# KitchenLightsController.net
KiCad netlist of a schematic drawn in EAGLE
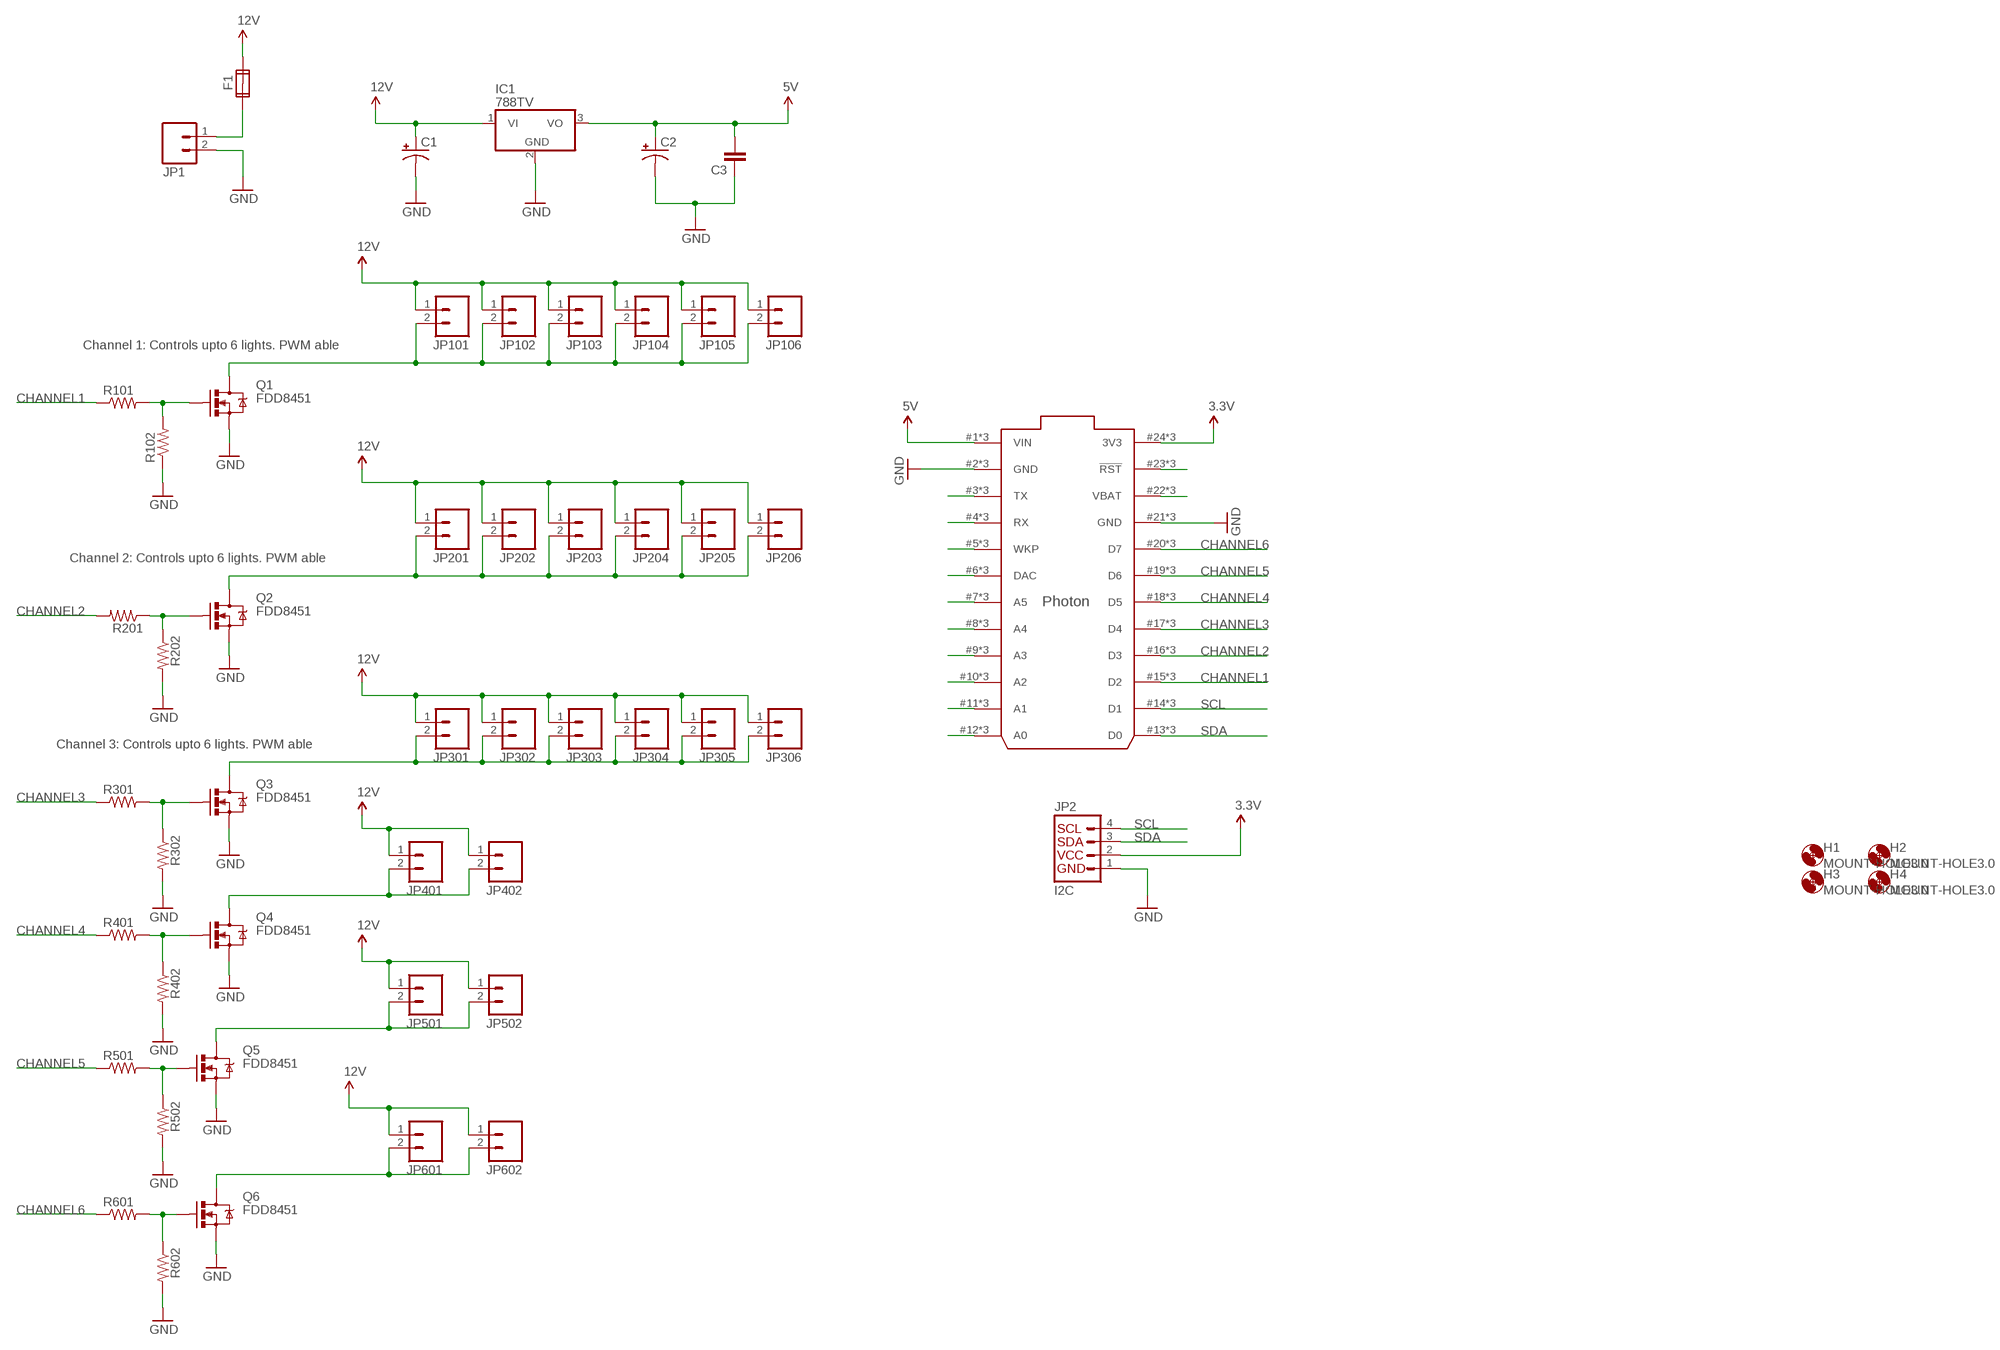
[diagram p0: schematic, sheet 1, part 1 of 2]
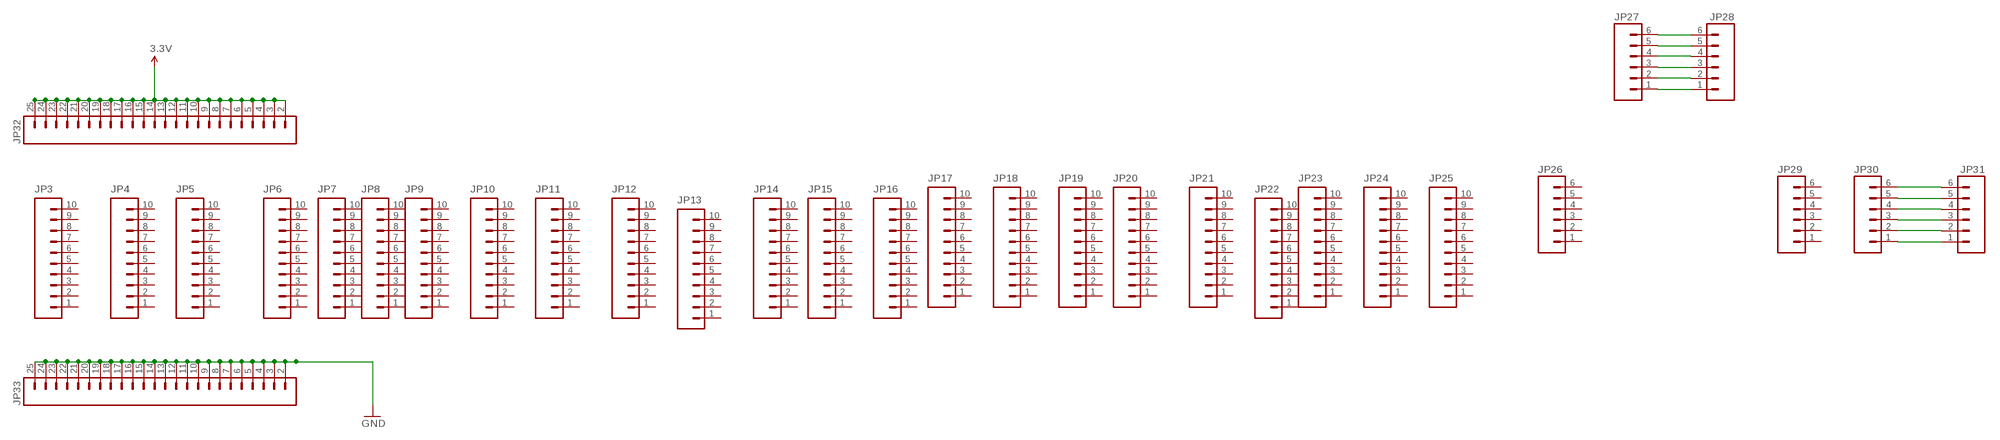
[diagram p1: schematic, sheet 1, part 2 of 2]

(export (version "E")
  (design (tool "Eeschema 10.0.6"))
  (components
    (comp (ref "C1")
      (value "10UF-25V-20%(PTH)")
      (footprint "eagle-import:CPOL-RADIAL-10UF-25V")
      (libsource (lib "eagle-import") (part "10UF-25V-20%(PTH)"))
    )
    (comp (ref "C2")
      (value "10UF-25V-20%(PTH)")
      (footprint "eagle-import:CPOL-RADIAL-10UF-25V")
      (libsource (lib "eagle-import") (part "10UF-25V-20%(PTH)"))
    )
    (comp (ref "C3")
      (value "1UF-25V-10%(0805)\"")
      (footprint "eagle-import:0805-CAP")
      (libsource (lib "eagle-import") (part "1UF-25V-10%(0805){dblquote}"))
    )
    (comp (ref "F1")
      (value "FUSE2P")
      (footprint "eagle-import:FUSE1")
      (libsource (lib "eagle-import") (part "FUSE2P"))
    )
    (comp (ref "H1")
      (value "MOUNT-HOLE3.0")
      (footprint "eagle-import:3,0")
      (libsource (lib "eagle-import") (part "MOUNT-HOLE3.0"))
    )
    (comp (ref "H2")
      (value "MOUNT-HOLE3.0")
      (footprint "eagle-import:3,0")
      (libsource (lib "eagle-import") (part "MOUNT-HOLE3.0"))
    )
    (comp (ref "H3")
      (value "MOUNT-HOLE3.0")
      (footprint "eagle-import:3,0")
      (libsource (lib "eagle-import") (part "MOUNT-HOLE3.0"))
    )
    (comp (ref "H4")
      (value "MOUNT-HOLE3.0")
      (footprint "eagle-import:3,0")
      (libsource (lib "eagle-import") (part "MOUNT-HOLE3.0"))
    )
    (comp (ref "IC1")
      (value "788TV")
      (footprint "eagle-import:TO220V")
      (libsource (lib "eagle-import") (part "78TV8"))
    )
    (comp (ref "JP1")
      (value "M023.5MM")
      (footprint "eagle-import:SCREWTERMINAL-3.5MM-2")
      (libsource (lib "eagle-import") (part "M023.5MM"))
    )
    (comp (ref "JP2")
      (value "I2C")
      (footprint "eagle-import:1X04")
      (libsource (lib "eagle-import") (part "I2C_STANDARD"))
    )
    (comp (ref "JP3")
      (value "M10NO_SILK_PTH_FEMALE")
      (footprint "eagle-import:1X10_NO_SILK")
      (libsource (lib "eagle-import") (part "M10NO_SILK_PTH_FEMALE"))
    )
    (comp (ref "JP4")
      (value "M10NO_SILK_PTH_FEMALE")
      (footprint "eagle-import:1X10_NO_SILK")
      (libsource (lib "eagle-import") (part "M10NO_SILK_PTH_FEMALE"))
    )
    (comp (ref "JP5")
      (value "M10NO_SILK_PTH_FEMALE")
      (footprint "eagle-import:1X10_NO_SILK")
      (libsource (lib "eagle-import") (part "M10NO_SILK_PTH_FEMALE"))
    )
    (comp (ref "JP6")
      (value "M10NO_SILK_PTH_FEMALE")
      (footprint "eagle-import:1X10_NO_SILK")
      (libsource (lib "eagle-import") (part "M10NO_SILK_PTH_FEMALE"))
    )
    (comp (ref "JP7")
      (value "M10NO_SILK_PTH_FEMALE")
      (footprint "eagle-import:1X10_NO_SILK")
      (libsource (lib "eagle-import") (part "M10NO_SILK_PTH_FEMALE"))
    )
    (comp (ref "JP8")
      (value "M10NO_SILK_PTH_FEMALE")
      (footprint "eagle-import:1X10_NO_SILK")
      (libsource (lib "eagle-import") (part "M10NO_SILK_PTH_FEMALE"))
    )
    (comp (ref "JP9")
      (value "M10NO_SILK_PTH_FEMALE")
      (footprint "eagle-import:1X10_NO_SILK")
      (libsource (lib "eagle-import") (part "M10NO_SILK_PTH_FEMALE"))
    )
    (comp (ref "JP10")
      (value "M10NO_SILK_PTH_FEMALE")
      (footprint "eagle-import:1X10_NO_SILK")
      (libsource (lib "eagle-import") (part "M10NO_SILK_PTH_FEMALE"))
    )
    (comp (ref "JP11")
      (value "M10NO_SILK_PTH_FEMALE")
      (footprint "eagle-import:1X10_NO_SILK")
      (libsource (lib "eagle-import") (part "M10NO_SILK_PTH_FEMALE"))
    )
    (comp (ref "JP12")
      (value "M10NO_SILK_PTH_FEMALE")
      (footprint "eagle-import:1X10_NO_SILK")
      (libsource (lib "eagle-import") (part "M10NO_SILK_PTH_FEMALE"))
    )
    (comp (ref "JP13")
      (value "M10NO_SILK_PTH_FEMALE")
      (footprint "eagle-import:1X10_NO_SILK")
      (libsource (lib "eagle-import") (part "M10NO_SILK_PTH_FEMALE"))
    )
    (comp (ref "JP14")
      (value "M10NO_SILK_PTH_FEMALE")
      (footprint "eagle-import:1X10_NO_SILK")
      (libsource (lib "eagle-import") (part "M10NO_SILK_PTH_FEMALE"))
    )
    (comp (ref "JP15")
      (value "M10NO_SILK_PTH_FEMALE")
      (footprint "eagle-import:1X10_NO_SILK")
      (libsource (lib "eagle-import") (part "M10NO_SILK_PTH_FEMALE"))
    )
    (comp (ref "JP16")
      (value "M10NO_SILK_PTH_FEMALE")
      (footprint "eagle-import:1X10_NO_SILK")
      (libsource (lib "eagle-import") (part "M10NO_SILK_PTH_FEMALE"))
    )
    (comp (ref "JP17")
      (value "M10NO_SILK_PTH_FEMALE")
      (footprint "eagle-import:1X10_NO_SILK")
      (libsource (lib "eagle-import") (part "M10NO_SILK_PTH_FEMALE"))
    )
    (comp (ref "JP18")
      (value "M10NO_SILK_PTH_FEMALE")
      (footprint "eagle-import:1X10_NO_SILK")
      (libsource (lib "eagle-import") (part "M10NO_SILK_PTH_FEMALE"))
    )
    (comp (ref "JP19")
      (value "M10NO_SILK_PTH_FEMALE")
      (footprint "eagle-import:1X10_NO_SILK")
      (libsource (lib "eagle-import") (part "M10NO_SILK_PTH_FEMALE"))
    )
    (comp (ref "JP20")
      (value "M10NO_SILK_PTH_FEMALE")
      (footprint "eagle-import:1X10_NO_SILK")
      (libsource (lib "eagle-import") (part "M10NO_SILK_PTH_FEMALE"))
    )
    (comp (ref "JP21")
      (value "M10NO_SILK_PTH_FEMALE")
      (footprint "eagle-import:1X10_NO_SILK")
      (libsource (lib "eagle-import") (part "M10NO_SILK_PTH_FEMALE"))
    )
    (comp (ref "JP22")
      (value "M10NO_SILK_PTH_FEMALE")
      (footprint "eagle-import:1X10_NO_SILK")
      (libsource (lib "eagle-import") (part "M10NO_SILK_PTH_FEMALE"))
    )
    (comp (ref "JP23")
      (value "M10NO_SILK_PTH_FEMALE")
      (footprint "eagle-import:1X10_NO_SILK")
      (libsource (lib "eagle-import") (part "M10NO_SILK_PTH_FEMALE"))
    )
    (comp (ref "JP24")
      (value "M10NO_SILK_PTH_FEMALE")
      (footprint "eagle-import:1X10_NO_SILK")
      (libsource (lib "eagle-import") (part "M10NO_SILK_PTH_FEMALE"))
    )
    (comp (ref "JP25")
      (value "M10NO_SILK_PTH_FEMALE")
      (footprint "eagle-import:1X10_NO_SILK")
      (libsource (lib "eagle-import") (part "M10NO_SILK_PTH_FEMALE"))
    )
    (comp (ref "JP26")
      (value "M06NO_SILK_FEMALE_PTH")
      (footprint "eagle-import:1X06_NO_SILK")
      (libsource (lib "eagle-import") (part "M06NO_SILK_FEMALE_PTH"))
    )
    (comp (ref "JP27")
      (value "M06NO_SILK_FEMALE_PTH")
      (footprint "eagle-import:1X06_NO_SILK")
      (libsource (lib "eagle-import") (part "M06NO_SILK_FEMALE_PTH"))
    )
    (comp (ref "JP28")
      (value "M06NO_SILK_FEMALE_PTH")
      (footprint "eagle-import:1X06_NO_SILK")
      (libsource (lib "eagle-import") (part "M06NO_SILK_FEMALE_PTH"))
    )
    (comp (ref "JP29")
      (value "M06NO_SILK_FEMALE_PTH")
      (footprint "eagle-import:1X06_NO_SILK")
      (libsource (lib "eagle-import") (part "M06NO_SILK_FEMALE_PTH"))
    )
    (comp (ref "JP30")
      (value "M06NO_SILK_FEMALE_PTH")
      (footprint "eagle-import:1X06_NO_SILK")
      (libsource (lib "eagle-import") (part "M06NO_SILK_FEMALE_PTH"))
    )
    (comp (ref "JP31")
      (value "M06NO_SILK_FEMALE_PTH")
      (footprint "eagle-import:1X06_NO_SILK")
      (libsource (lib "eagle-import") (part "M06NO_SILK_FEMALE_PTH"))
    )
    (comp (ref "JP32")
      (value "M24")
      (footprint "eagle-import:1X24")
      (libsource (lib "eagle-import") (part "M24"))
    )
    (comp (ref "JP33")
      (value "M24")
      (footprint "eagle-import:1X24")
      (libsource (lib "eagle-import") (part "M24"))
    )
    (comp (ref "JP101")
      (value "M02POLAR")
      (footprint "eagle-import:MOLEX-1X2")
      (libsource (lib "eagle-import") (part "M02POLAR"))
    )
    (comp (ref "JP102")
      (value "M02POLAR")
      (footprint "eagle-import:MOLEX-1X2")
      (libsource (lib "eagle-import") (part "M02POLAR"))
    )
    (comp (ref "JP103")
      (value "M02POLAR")
      (footprint "eagle-import:MOLEX-1X2")
      (libsource (lib "eagle-import") (part "M02POLAR"))
    )
    (comp (ref "JP104")
      (value "M02POLAR")
      (footprint "eagle-import:MOLEX-1X2")
      (libsource (lib "eagle-import") (part "M02POLAR"))
    )
    (comp (ref "JP105")
      (value "M02POLAR")
      (footprint "eagle-import:MOLEX-1X2")
      (libsource (lib "eagle-import") (part "M02POLAR"))
    )
    (comp (ref "JP106")
      (value "M02POLAR")
      (footprint "eagle-import:MOLEX-1X2")
      (libsource (lib "eagle-import") (part "M02POLAR"))
    )
    (comp (ref "JP201")
      (value "M02POLAR")
      (footprint "eagle-import:MOLEX-1X2")
      (libsource (lib "eagle-import") (part "M02POLAR"))
    )
    (comp (ref "JP202")
      (value "M02POLAR")
      (footprint "eagle-import:MOLEX-1X2")
      (libsource (lib "eagle-import") (part "M02POLAR"))
    )
    (comp (ref "JP203")
      (value "M02POLAR")
      (footprint "eagle-import:MOLEX-1X2")
      (libsource (lib "eagle-import") (part "M02POLAR"))
    )
    (comp (ref "JP204")
      (value "M02POLAR")
      (footprint "eagle-import:MOLEX-1X2")
      (libsource (lib "eagle-import") (part "M02POLAR"))
    )
    (comp (ref "JP205")
      (value "M02POLAR")
      (footprint "eagle-import:MOLEX-1X2")
      (libsource (lib "eagle-import") (part "M02POLAR"))
    )
    (comp (ref "JP206")
      (value "M02POLAR")
      (footprint "eagle-import:MOLEX-1X2")
      (libsource (lib "eagle-import") (part "M02POLAR"))
    )
    (comp (ref "JP301")
      (value "M02POLAR")
      (footprint "eagle-import:MOLEX-1X2")
      (libsource (lib "eagle-import") (part "M02POLAR"))
    )
    (comp (ref "JP302")
      (value "M02POLAR")
      (footprint "eagle-import:MOLEX-1X2")
      (libsource (lib "eagle-import") (part "M02POLAR"))
    )
    (comp (ref "JP303")
      (value "M02POLAR")
      (footprint "eagle-import:MOLEX-1X2")
      (libsource (lib "eagle-import") (part "M02POLAR"))
    )
    (comp (ref "JP304")
      (value "M02POLAR")
      (footprint "eagle-import:MOLEX-1X2")
      (libsource (lib "eagle-import") (part "M02POLAR"))
    )
    (comp (ref "JP305")
      (value "M02POLAR")
      (footprint "eagle-import:MOLEX-1X2")
      (libsource (lib "eagle-import") (part "M02POLAR"))
    )
    (comp (ref "JP306")
      (value "M02POLAR")
      (footprint "eagle-import:MOLEX-1X2")
      (libsource (lib "eagle-import") (part "M02POLAR"))
    )
    (comp (ref "JP401")
      (value "M02POLAR")
      (footprint "eagle-import:MOLEX-1X2")
      (libsource (lib "eagle-import") (part "M02POLAR"))
    )
    (comp (ref "JP402")
      (value "M023.5MM")
      (footprint "eagle-import:SCREWTERMINAL-3.5MM-2")
      (libsource (lib "eagle-import") (part "M023.5MM"))
    )
    (comp (ref "JP501")
      (value "M02POLAR")
      (footprint "eagle-import:MOLEX-1X2")
      (libsource (lib "eagle-import") (part "M02POLAR"))
    )
    (comp (ref "JP502")
      (value "M023.5MM")
      (footprint "eagle-import:SCREWTERMINAL-3.5MM-2")
      (libsource (lib "eagle-import") (part "M023.5MM"))
    )
    (comp (ref "JP601")
      (value "M02POLAR")
      (footprint "eagle-import:MOLEX-1X2")
      (libsource (lib "eagle-import") (part "M02POLAR"))
    )
    (comp (ref "JP602")
      (value "M023.5MM")
      (footprint "eagle-import:SCREWTERMINAL-3.5MM-2")
      (libsource (lib "eagle-import") (part "M023.5MM"))
    )
    (comp (ref "Q1")
      (value "FDD8451")
      (footprint "eagle-import:DPAK")
      (libsource (lib "eagle-import") (part "MOSFET-NCHANNELFDD8780"))
    )
    (comp (ref "Q2")
      (value "FDD8451")
      (footprint "eagle-import:DPAK")
      (libsource (lib "eagle-import") (part "MOSFET-NCHANNELFDD8780"))
    )
    (comp (ref "Q3")
      (value "FDD8451")
      (footprint "eagle-import:DPAK")
      (libsource (lib "eagle-import") (part "MOSFET-NCHANNELFDD8780"))
    )
    (comp (ref "Q4")
      (value "FDD8451")
      (footprint "eagle-import:DPAK")
      (libsource (lib "eagle-import") (part "MOSFET-NCHANNELFDD8780"))
    )
    (comp (ref "Q5")
      (value "FDD8451")
      (footprint "eagle-import:DPAK")
      (libsource (lib "eagle-import") (part "MOSFET-NCHANNELFDD8780"))
    )
    (comp (ref "Q6")
      (value "FDD8451")
      (footprint "eagle-import:DPAK")
      (libsource (lib "eagle-import") (part "MOSFET-NCHANNELFDD8780"))
    )
    (comp (ref "R101")
      (value "RESISTOR0805-RES")
      (footprint "eagle-import:0805")
      (libsource (lib "eagle-import") (part "RESISTOR0805-RES"))
    )
    (comp (ref "R102")
      (value "RESISTOR0805-RES")
      (footprint "eagle-import:0805")
      (libsource (lib "eagle-import") (part "RESISTOR0805-RES"))
    )
    (comp (ref "R201")
      (value "RESISTOR0805-RES")
      (footprint "eagle-import:0805")
      (libsource (lib "eagle-import") (part "RESISTOR0805-RES"))
    )
    (comp (ref "R202")
      (value "RESISTOR0805-RES")
      (footprint "eagle-import:0805")
      (libsource (lib "eagle-import") (part "RESISTOR0805-RES"))
    )
    (comp (ref "R301")
      (value "RESISTOR0805-RES")
      (footprint "eagle-import:0805")
      (libsource (lib "eagle-import") (part "RESISTOR0805-RES"))
    )
    (comp (ref "R302")
      (value "RESISTOR0805-RES")
      (footprint "eagle-import:0805")
      (libsource (lib "eagle-import") (part "RESISTOR0805-RES"))
    )
    (comp (ref "R401")
      (value "RESISTOR0805-RES")
      (footprint "eagle-import:0805")
      (libsource (lib "eagle-import") (part "RESISTOR0805-RES"))
    )
    (comp (ref "R402")
      (value "RESISTOR0805-RES")
      (footprint "eagle-import:0805")
      (libsource (lib "eagle-import") (part "RESISTOR0805-RES"))
    )
    (comp (ref "R501")
      (value "RESISTOR0805-RES")
      (footprint "eagle-import:0805")
      (libsource (lib "eagle-import") (part "RESISTOR0805-RES"))
    )
    (comp (ref "R502")
      (value "RESISTOR0805-RES")
      (footprint "eagle-import:0805")
      (libsource (lib "eagle-import") (part "RESISTOR0805-RES"))
    )
    (comp (ref "R601")
      (value "RESISTOR0805-RES")
      (footprint "eagle-import:0805")
      (libsource (lib "eagle-import") (part "RESISTOR0805-RES"))
    )
    (comp (ref "R602")
      (value "RESISTOR0805-RES")
      (footprint "eagle-import:0805")
      (libsource (lib "eagle-import") (part "RESISTOR0805-RES"))
    )
    (comp (ref "U$1")
      (value "PHOTON_WITH_STACKABLE_HEADERS")
      (footprint "eagle-import:PHOTON_STACKABLE")
      (libsource (lib "eagle-import") (part "PHOTON_WITH_STACKABLE_HEADERS"))
    )
  )
  (nets
    (net (code "1") (name "/CHANNEL1") (class "Default")
      (node (ref "R101") (pin "1") (pinfunction "1_1") (pintype "passive"))
      (node (ref "U$1") (pin "#15") (pinfunction "D2_#15") (pintype "bidirectional"))
      (node (ref "U$1") (pin "15") (pinfunction "D2_15") (pintype "bidirectional"))
      (node (ref "U$1") (pin "@15") (pinfunction "D2_@15") (pintype "bidirectional"))
    )
    (net (code "2") (name "/CHANNEL2") (class "Default")
      (node (ref "R201") (pin "2") (pinfunction "2_2") (pintype "passive"))
      (node (ref "U$1") (pin "#16") (pinfunction "D3_#16") (pintype "bidirectional"))
      (node (ref "U$1") (pin "16") (pinfunction "D3_16") (pintype "bidirectional"))
      (node (ref "U$1") (pin "@16") (pinfunction "D3_@16") (pintype "bidirectional"))
    )
    (net (code "3") (name "/CHANNEL3") (class "Default")
      (node (ref "R301") (pin "1") (pinfunction "1_1") (pintype "passive"))
      (node (ref "U$1") (pin "#17") (pinfunction "D4_#17") (pintype "bidirectional"))
      (node (ref "U$1") (pin "17") (pinfunction "D4_17") (pintype "bidirectional"))
      (node (ref "U$1") (pin "@17") (pinfunction "D4_@17") (pintype "bidirectional"))
    )
    (net (code "4") (name "/CHANNEL4") (class "Default")
      (node (ref "R401") (pin "1") (pinfunction "1_1") (pintype "passive"))
      (node (ref "U$1") (pin "#18") (pinfunction "D5_#18") (pintype "bidirectional"))
      (node (ref "U$1") (pin "18") (pinfunction "D5_18") (pintype "bidirectional"))
      (node (ref "U$1") (pin "@18") (pinfunction "D5_@18") (pintype "bidirectional"))
    )
    (net (code "5") (name "/CHANNEL5") (class "Default")
      (node (ref "R501") (pin "1") (pinfunction "1_1") (pintype "passive"))
      (node (ref "U$1") (pin "#19") (pinfunction "D6_#19") (pintype "bidirectional"))
      (node (ref "U$1") (pin "19") (pinfunction "D6_19") (pintype "bidirectional"))
      (node (ref "U$1") (pin "@19") (pinfunction "D6_@19") (pintype "bidirectional"))
    )
    (net (code "6") (name "/CHANNEL6") (class "Default")
      (node (ref "R601") (pin "1") (pinfunction "1_1") (pintype "passive"))
      (node (ref "U$1") (pin "#20") (pinfunction "D7_#20") (pintype "bidirectional"))
      (node (ref "U$1") (pin "20") (pinfunction "D7_20") (pintype "bidirectional"))
      (node (ref "U$1") (pin "@20") (pinfunction "D7_@20") (pintype "bidirectional"))
    )
    (net (code "7") (name "/SCL") (class "Default")
      (node (ref "JP2") (pin "4") (pinfunction "4_4") (pintype "passive"))
      (node (ref "U$1") (pin "#14") (pinfunction "D1_#14") (pintype "bidirectional"))
      (node (ref "U$1") (pin "14") (pinfunction "D1_14") (pintype "bidirectional"))
      (node (ref "U$1") (pin "@14") (pinfunction "D1_@14") (pintype "bidirectional"))
    )
    (net (code "8") (name "/SDA") (class "Default")
      (node (ref "JP2") (pin "3") (pinfunction "3_3") (pintype "passive"))
      (node (ref "U$1") (pin "#13") (pinfunction "D0_#13") (pintype "bidirectional"))
      (node (ref "U$1") (pin "13") (pinfunction "D0_13") (pintype "bidirectional"))
      (node (ref "U$1") (pin "@13") (pinfunction "D0_@13") (pintype "bidirectional"))
    )
    (net (code "9") (name "3.3V") (class "Default")
      (node (ref "JP2") (pin "2") (pinfunction "2_2") (pintype "passive"))
      (node (ref "JP32") (pin "10") (pinfunction "10_10") (pintype "passive"))
      (node (ref "JP32") (pin "11") (pinfunction "11_11") (pintype "passive"))
      (node (ref "JP32") (pin "12") (pinfunction "12_12") (pintype "passive"))
      (node (ref "JP32") (pin "13") (pinfunction "13_13") (pintype "passive"))
      (node (ref "JP32") (pin "14") (pinfunction "14_14") (pintype "passive"))
      (node (ref "JP32") (pin "15") (pinfunction "15_15") (pintype "passive"))
      (node (ref "JP32") (pin "16") (pinfunction "16_16") (pintype "passive"))
      (node (ref "JP32") (pin "17") (pinfunction "17_17") (pintype "passive"))
      (node (ref "JP32") (pin "18") (pinfunction "18_18") (pintype "passive"))
      (node (ref "JP32") (pin "19") (pinfunction "19_19") (pintype "passive"))
      (node (ref "JP32") (pin "2") (pinfunction "2_2") (pintype "passive"))
      (node (ref "JP32") (pin "20") (pinfunction "20_20") (pintype "passive"))
      (node (ref "JP32") (pin "21") (pinfunction "21_21") (pintype "passive"))
      (node (ref "JP32") (pin "22") (pinfunction "22_22") (pintype "passive"))
      (node (ref "JP32") (pin "23") (pinfunction "23_23") (pintype "passive"))
      (node (ref "JP32") (pin "24") (pinfunction "24_24") (pintype "passive"))
      (node (ref "JP32") (pin "25") (pinfunction "25_25") (pintype "passive"))
      (node (ref "JP32") (pin "3") (pinfunction "3_3") (pintype "passive"))
      (node (ref "JP32") (pin "4") (pinfunction "4_4") (pintype "passive"))
      (node (ref "JP32") (pin "5") (pinfunction "5_5") (pintype "passive"))
      (node (ref "JP32") (pin "6") (pinfunction "6_6") (pintype "passive"))
      (node (ref "JP32") (pin "7") (pinfunction "7_7") (pintype "passive"))
      (node (ref "JP32") (pin "8") (pinfunction "8_8") (pintype "passive"))
      (node (ref "JP32") (pin "9") (pinfunction "9_9") (pintype "passive"))
      (node (ref "U$1") (pin "#24") (pinfunction "3V3_#24") (pintype "power_in"))
      (node (ref "U$1") (pin "24") (pinfunction "3V3_24") (pintype "power_in"))
      (node (ref "U$1") (pin "@24") (pinfunction "3V3_@24") (pintype "power_in"))
    )
    (net (code "10") (name "5V") (class "Default")
      (node (ref "C2") (pin "1") (pinfunction "+_1") (pintype "passive"))
      (node (ref "C3") (pin "2") (pinfunction "2_2") (pintype "passive"))
      (node (ref "IC1") (pin "3") (pinfunction "VO_3") (pintype "passive"))
      (node (ref "U$1") (pin "#1") (pinfunction "VIN_#1") (pintype "power_in"))
      (node (ref "U$1") (pin "1") (pinfunction "VIN_1") (pintype "power_in"))
      (node (ref "U$1") (pin "@1") (pinfunction "VIN_@1") (pintype "power_in"))
    )
    (net (code "11") (name "12V") (class "Default")
      (node (ref "C1") (pin "1") (pinfunction "+_1") (pintype "passive"))
      (node (ref "F1") (pin "2A") (pinfunction "2A_2A") (pintype "passive"))
      (node (ref "IC1") (pin "1") (pinfunction "VI_1") (pintype "input"))
      (node (ref "JP101") (pin "1") (pinfunction "1_1") (pintype "passive"))
      (node (ref "JP102") (pin "1") (pinfunction "1_1") (pintype "passive"))
      (node (ref "JP103") (pin "1") (pinfunction "1_1") (pintype "passive"))
      (node (ref "JP104") (pin "1") (pinfunction "1_1") (pintype "passive"))
      (node (ref "JP105") (pin "1") (pinfunction "1_1") (pintype "passive"))
      (node (ref "JP106") (pin "1") (pinfunction "1_1") (pintype "passive"))
      (node (ref "JP201") (pin "1") (pinfunction "1_1") (pintype "passive"))
      (node (ref "JP202") (pin "1") (pinfunction "1_1") (pintype "passive"))
      (node (ref "JP203") (pin "1") (pinfunction "1_1") (pintype "passive"))
      (node (ref "JP204") (pin "1") (pinfunction "1_1") (pintype "passive"))
      (node (ref "JP205") (pin "1") (pinfunction "1_1") (pintype "passive"))
      (node (ref "JP206") (pin "1") (pinfunction "1_1") (pintype "passive"))
      (node (ref "JP301") (pin "1") (pinfunction "1_1") (pintype "passive"))
      (node (ref "JP302") (pin "1") (pinfunction "1_1") (pintype "passive"))
      (node (ref "JP303") (pin "1") (pinfunction "1_1") (pintype "passive"))
      (node (ref "JP304") (pin "1") (pinfunction "1_1") (pintype "passive"))
      (node (ref "JP305") (pin "1") (pinfunction "1_1") (pintype "passive"))
      (node (ref "JP306") (pin "1") (pinfunction "1_1") (pintype "passive"))
      (node (ref "JP401") (pin "1") (pinfunction "1_1") (pintype "passive"))
      (node (ref "JP402") (pin "1") (pinfunction "1_1") (pintype "passive"))
      (node (ref "JP501") (pin "1") (pinfunction "1_1") (pintype "passive"))
      (node (ref "JP502") (pin "1") (pinfunction "1_1") (pintype "passive"))
      (node (ref "JP601") (pin "1") (pinfunction "1_1") (pintype "passive"))
      (node (ref "JP602") (pin "1") (pinfunction "1_1") (pintype "passive"))
    )
    (net (code "12") (name "GND") (class "Default")
      (node (ref "C1") (pin "2") (pinfunction "-_2") (pintype "passive"))
      (node (ref "C2") (pin "2") (pinfunction "-_2") (pintype "passive"))
      (node (ref "C3") (pin "1") (pinfunction "1_1") (pintype "passive"))
      (node (ref "IC1") (pin "2") (pinfunction "GND_2") (pintype "passive"))
      (node (ref "JP1") (pin "2") (pinfunction "2_2") (pintype "passive"))
      (node (ref "JP2") (pin "1") (pinfunction "1_1") (pintype "passive"))
      (node (ref "JP33") (pin "10") (pinfunction "10_10") (pintype "passive"))
      (node (ref "JP33") (pin "11") (pinfunction "11_11") (pintype "passive"))
      (node (ref "JP33") (pin "12") (pinfunction "12_12") (pintype "passive"))
      (node (ref "JP33") (pin "13") (pinfunction "13_13") (pintype "passive"))
      (node (ref "JP33") (pin "14") (pinfunction "14_14") (pintype "passive"))
      (node (ref "JP33") (pin "15") (pinfunction "15_15") (pintype "passive"))
      (node (ref "JP33") (pin "16") (pinfunction "16_16") (pintype "passive"))
      (node (ref "JP33") (pin "17") (pinfunction "17_17") (pintype "passive"))
      (node (ref "JP33") (pin "18") (pinfunction "18_18") (pintype "passive"))
      (node (ref "JP33") (pin "19") (pinfunction "19_19") (pintype "passive"))
      (node (ref "JP33") (pin "2") (pinfunction "2_2") (pintype "passive"))
      (node (ref "JP33") (pin "20") (pinfunction "20_20") (pintype "passive"))
      (node (ref "JP33") (pin "21") (pinfunction "21_21") (pintype "passive"))
      (node (ref "JP33") (pin "22") (pinfunction "22_22") (pintype "passive"))
      (node (ref "JP33") (pin "23") (pinfunction "23_23") (pintype "passive"))
      (node (ref "JP33") (pin "24") (pinfunction "24_24") (pintype "passive"))
      (node (ref "JP33") (pin "25") (pinfunction "25_25") (pintype "passive"))
      (node (ref "JP33") (pin "3") (pinfunction "3_3") (pintype "passive"))
      (node (ref "JP33") (pin "4") (pinfunction "4_4") (pintype "passive"))
      (node (ref "JP33") (pin "5") (pinfunction "5_5") (pintype "passive"))
      (node (ref "JP33") (pin "6") (pinfunction "6_6") (pintype "passive"))
      (node (ref "JP33") (pin "7") (pinfunction "7_7") (pintype "passive"))
      (node (ref "JP33") (pin "8") (pinfunction "8_8") (pintype "passive"))
      (node (ref "JP33") (pin "9") (pinfunction "9_9") (pintype "passive"))
      (node (ref "Q1") (pin "3") (pinfunction "S_3") (pintype "passive"))
      (node (ref "Q2") (pin "3") (pinfunction "S_3") (pintype "passive"))
      (node (ref "Q3") (pin "3") (pinfunction "S_3") (pintype "passive"))
      (node (ref "Q4") (pin "3") (pinfunction "S_3") (pintype "passive"))
      (node (ref "Q5") (pin "3") (pinfunction "S_3") (pintype "passive"))
      (node (ref "Q6") (pin "3") (pinfunction "S_3") (pintype "passive"))
      (node (ref "R102") (pin "1") (pinfunction "1_1") (pintype "passive"))
      (node (ref "R202") (pin "2") (pinfunction "2_2") (pintype "passive"))
      (node (ref "R302") (pin "2") (pinfunction "2_2") (pintype "passive"))
      (node (ref "R402") (pin "2") (pinfunction "2_2") (pintype "passive"))
      (node (ref "R502") (pin "2") (pinfunction "2_2") (pintype "passive"))
      (node (ref "R602") (pin "2") (pinfunction "2_2") (pintype "passive"))
      (node (ref "U$1") (pin "#2") (pinfunction "GND_#2") (pintype "power_in"))
      (node (ref "U$1") (pin "#21") (pinfunction "GND_#21") (pintype "power_in"))
      (node (ref "U$1") (pin "2") (pinfunction "GND_2") (pintype "power_in"))
      (node (ref "U$1") (pin "21") (pinfunction "GND_21") (pintype "power_in"))
      (node (ref "U$1") (pin "@2") (pinfunction "GND_@2") (pintype "power_in"))
      (node (ref "U$1") (pin "@21") (pinfunction "GND_@21") (pintype "power_in"))
    )
    (net (code "13") (name "Net-(F1-Pad1A)") (class "Default")
      (node (ref "F1") (pin "1A") (pinfunction "1A_1A") (pintype "passive"))
      (node (ref "JP1") (pin "1") (pinfunction "1_1") (pintype "passive"))
    )
    (net (code "14") (name "Net-(JP27-Pad1)") (class "Default")
      (node (ref "JP27") (pin "1") (pinfunction "1_1") (pintype "passive"))
      (node (ref "JP28") (pin "1") (pinfunction "1_1") (pintype "passive"))
    )
    (net (code "15") (name "Net-(JP27-Pad2)") (class "Default")
      (node (ref "JP27") (pin "2") (pinfunction "2_2") (pintype "passive"))
      (node (ref "JP28") (pin "2") (pinfunction "2_2") (pintype "passive"))
    )
    (net (code "16") (name "Net-(JP27-Pad3)") (class "Default")
      (node (ref "JP27") (pin "3") (pinfunction "3_3") (pintype "passive"))
      (node (ref "JP28") (pin "3") (pinfunction "3_3") (pintype "passive"))
    )
    (net (code "17") (name "Net-(JP27-Pad4)") (class "Default")
      (node (ref "JP27") (pin "4") (pinfunction "4_4") (pintype "passive"))
      (node (ref "JP28") (pin "4") (pinfunction "4_4") (pintype "passive"))
    )
    (net (code "18") (name "Net-(JP27-Pad5)") (class "Default")
      (node (ref "JP27") (pin "5") (pinfunction "5_5") (pintype "passive"))
      (node (ref "JP28") (pin "5") (pinfunction "5_5") (pintype "passive"))
    )
    (net (code "19") (name "Net-(JP27-Pad6)") (class "Default")
      (node (ref "JP27") (pin "6") (pinfunction "6_6") (pintype "passive"))
      (node (ref "JP28") (pin "6") (pinfunction "6_6") (pintype "passive"))
    )
    (net (code "20") (name "Net-(JP30-Pad1)") (class "Default")
      (node (ref "JP30") (pin "1") (pinfunction "1_1") (pintype "passive"))
      (node (ref "JP31") (pin "1") (pinfunction "1_1") (pintype "passive"))
    )
    (net (code "21") (name "Net-(JP30-Pad2)") (class "Default")
      (node (ref "JP30") (pin "2") (pinfunction "2_2") (pintype "passive"))
      (node (ref "JP31") (pin "2") (pinfunction "2_2") (pintype "passive"))
    )
    (net (code "22") (name "Net-(JP30-Pad3)") (class "Default")
      (node (ref "JP30") (pin "3") (pinfunction "3_3") (pintype "passive"))
      (node (ref "JP31") (pin "3") (pinfunction "3_3") (pintype "passive"))
    )
    (net (code "23") (name "Net-(JP30-Pad4)") (class "Default")
      (node (ref "JP30") (pin "4") (pinfunction "4_4") (pintype "passive"))
      (node (ref "JP31") (pin "4") (pinfunction "4_4") (pintype "passive"))
    )
    (net (code "24") (name "Net-(JP30-Pad5)") (class "Default")
      (node (ref "JP30") (pin "5") (pinfunction "5_5") (pintype "passive"))
      (node (ref "JP31") (pin "5") (pinfunction "5_5") (pintype "passive"))
    )
    (net (code "25") (name "Net-(JP30-Pad6)") (class "Default")
      (node (ref "JP30") (pin "6") (pinfunction "6_6") (pintype "passive"))
      (node (ref "JP31") (pin "6") (pinfunction "6_6") (pintype "passive"))
    )
    (net (code "26") (name "Net-(Q1-D)") (class "Default")
      (node (ref "JP101") (pin "2") (pinfunction "2_2") (pintype "passive"))
      (node (ref "JP102") (pin "2") (pinfunction "2_2") (pintype "passive"))
      (node (ref "JP103") (pin "2") (pinfunction "2_2") (pintype "passive"))
      (node (ref "JP104") (pin "2") (pinfunction "2_2") (pintype "passive"))
      (node (ref "JP105") (pin "2") (pinfunction "2_2") (pintype "passive"))
      (node (ref "JP106") (pin "2") (pinfunction "2_2") (pintype "passive"))
      (node (ref "Q1") (pin "4") (pinfunction "D_4") (pintype "passive"))
    )
    (net (code "27") (name "Net-(Q1-G)") (class "Default")
      (node (ref "Q1") (pin "1") (pinfunction "G_1") (pintype "passive"))
      (node (ref "R101") (pin "2") (pinfunction "2_2") (pintype "passive"))
      (node (ref "R102") (pin "2") (pinfunction "2_2") (pintype "passive"))
    )
    (net (code "28") (name "Net-(Q2-D)") (class "Default")
      (node (ref "JP201") (pin "2") (pinfunction "2_2") (pintype "passive"))
      (node (ref "JP202") (pin "2") (pinfunction "2_2") (pintype "passive"))
      (node (ref "JP203") (pin "2") (pinfunction "2_2") (pintype "passive"))
      (node (ref "JP204") (pin "2") (pinfunction "2_2") (pintype "passive"))
      (node (ref "JP205") (pin "2") (pinfunction "2_2") (pintype "passive"))
      (node (ref "JP206") (pin "2") (pinfunction "2_2") (pintype "passive"))
      (node (ref "Q2") (pin "4") (pinfunction "D_4") (pintype "passive"))
    )
    (net (code "29") (name "Net-(Q2-G)") (class "Default")
      (node (ref "Q2") (pin "1") (pinfunction "G_1") (pintype "passive"))
      (node (ref "R201") (pin "1") (pinfunction "1_1") (pintype "passive"))
      (node (ref "R202") (pin "1") (pinfunction "1_1") (pintype "passive"))
    )
    (net (code "30") (name "Net-(Q3-D)") (class "Default")
      (node (ref "JP301") (pin "2") (pinfunction "2_2") (pintype "passive"))
      (node (ref "JP302") (pin "2") (pinfunction "2_2") (pintype "passive"))
      (node (ref "JP303") (pin "2") (pinfunction "2_2") (pintype "passive"))
      (node (ref "JP304") (pin "2") (pinfunction "2_2") (pintype "passive"))
      (node (ref "JP305") (pin "2") (pinfunction "2_2") (pintype "passive"))
      (node (ref "JP306") (pin "2") (pinfunction "2_2") (pintype "passive"))
      (node (ref "Q3") (pin "4") (pinfunction "D_4") (pintype "passive"))
    )
    (net (code "31") (name "Net-(Q3-G)") (class "Default")
      (node (ref "Q3") (pin "1") (pinfunction "G_1") (pintype "passive"))
      (node (ref "R301") (pin "2") (pinfunction "2_2") (pintype "passive"))
      (node (ref "R302") (pin "1") (pinfunction "1_1") (pintype "passive"))
    )
    (net (code "32") (name "Net-(Q4-D)") (class "Default")
      (node (ref "JP401") (pin "2") (pinfunction "2_2") (pintype "passive"))
      (node (ref "JP402") (pin "2") (pinfunction "2_2") (pintype "passive"))
      (node (ref "Q4") (pin "4") (pinfunction "D_4") (pintype "passive"))
    )
    (net (code "33") (name "Net-(Q4-G)") (class "Default")
      (node (ref "Q4") (pin "1") (pinfunction "G_1") (pintype "passive"))
      (node (ref "R401") (pin "2") (pinfunction "2_2") (pintype "passive"))
      (node (ref "R402") (pin "1") (pinfunction "1_1") (pintype "passive"))
    )
    (net (code "34") (name "Net-(Q5-D)") (class "Default")
      (node (ref "JP501") (pin "2") (pinfunction "2_2") (pintype "passive"))
      (node (ref "JP502") (pin "2") (pinfunction "2_2") (pintype "passive"))
      (node (ref "Q5") (pin "4") (pinfunction "D_4") (pintype "passive"))
    )
    (net (code "35") (name "Net-(Q5-G)") (class "Default")
      (node (ref "Q5") (pin "1") (pinfunction "G_1") (pintype "passive"))
      (node (ref "R501") (pin "2") (pinfunction "2_2") (pintype "passive"))
      (node (ref "R502") (pin "1") (pinfunction "1_1") (pintype "passive"))
    )
    (net (code "36") (name "Net-(Q6-D)") (class "Default")
      (node (ref "JP601") (pin "2") (pinfunction "2_2") (pintype "passive"))
      (node (ref "JP602") (pin "2") (pinfunction "2_2") (pintype "passive"))
      (node (ref "Q6") (pin "4") (pinfunction "D_4") (pintype "passive"))
    )
    (net (code "37") (name "Net-(Q6-G)") (class "Default")
      (node (ref "Q6") (pin "1") (pinfunction "G_1") (pintype "passive"))
      (node (ref "R601") (pin "2") (pinfunction "2_2") (pintype "passive"))
      (node (ref "R602") (pin "1") (pinfunction "1_1") (pintype "passive"))
    )
    (net (code "38") (name "Net-(U$1-A0-Pad#12)") (class "Default")
      (node (ref "U$1") (pin "#12") (pinfunction "A0_#12") (pintype "bidirectional"))
      (node (ref "U$1") (pin "12") (pinfunction "A0_12") (pintype "bidirectional"))
      (node (ref "U$1") (pin "@12") (pinfunction "A0_@12") (pintype "bidirectional"))
    )
    (net (code "39") (name "Net-(U$1-A1-Pad#11)") (class "Default")
      (node (ref "U$1") (pin "#11") (pinfunction "A1_#11") (pintype "bidirectional"))
      (node (ref "U$1") (pin "11") (pinfunction "A1_11") (pintype "bidirectional"))
      (node (ref "U$1") (pin "@11") (pinfunction "A1_@11") (pintype "bidirectional"))
    )
    (net (code "40") (name "Net-(U$1-A2-Pad#10)") (class "Default")
      (node (ref "U$1") (pin "#10") (pinfunction "A2_#10") (pintype "bidirectional"))
      (node (ref "U$1") (pin "10") (pinfunction "A2_10") (pintype "bidirectional"))
      (node (ref "U$1") (pin "@10") (pinfunction "A2_@10") (pintype "bidirectional"))
    )
    (net (code "41") (name "Net-(U$1-A3-Pad#9)") (class "Default")
      (node (ref "U$1") (pin "#9") (pinfunction "A3_#9") (pintype "bidirectional"))
      (node (ref "U$1") (pin "9") (pinfunction "A3_9") (pintype "bidirectional"))
      (node (ref "U$1") (pin "@9") (pinfunction "A3_@9") (pintype "bidirectional"))
    )
    (net (code "42") (name "Net-(U$1-A4-Pad#8)") (class "Default")
      (node (ref "U$1") (pin "#8") (pinfunction "A4_#8") (pintype "bidirectional"))
      (node (ref "U$1") (pin "8") (pinfunction "A4_8") (pintype "bidirectional"))
      (node (ref "U$1") (pin "@8") (pinfunction "A4_@8") (pintype "bidirectional"))
    )
    (net (code "43") (name "Net-(U$1-A5-Pad#7)") (class "Default")
      (node (ref "U$1") (pin "#7") (pinfunction "A5_#7") (pintype "bidirectional"))
      (node (ref "U$1") (pin "7") (pinfunction "A5_7") (pintype "bidirectional"))
      (node (ref "U$1") (pin "@7") (pinfunction "A5_@7") (pintype "bidirectional"))
    )
    (net (code "44") (name "Net-(U$1-DAC-Pad#6)") (class "Default")
      (node (ref "U$1") (pin "#6") (pinfunction "DAC_#6") (pintype "bidirectional"))
      (node (ref "U$1") (pin "6") (pinfunction "DAC_6") (pintype "bidirectional"))
      (node (ref "U$1") (pin "@6") (pinfunction "DAC_@6") (pintype "bidirectional"))
    )
    (net (code "45") (name "Net-(U$1-RX-Pad#4)") (class "Default")
      (node (ref "U$1") (pin "#4") (pinfunction "RX_#4") (pintype "bidirectional"))
      (node (ref "U$1") (pin "4") (pinfunction "RX_4") (pintype "bidirectional"))
      (node (ref "U$1") (pin "@4") (pinfunction "RX_@4") (pintype "bidirectional"))
    )
    (net (code "46") (name "Net-(U$1-TX-Pad#3)") (class "Default")
      (node (ref "U$1") (pin "#3") (pinfunction "TX_#3") (pintype "bidirectional"))
      (node (ref "U$1") (pin "3") (pinfunction "TX_3") (pintype "bidirectional"))
      (node (ref "U$1") (pin "@3") (pinfunction "TX_@3") (pintype "bidirectional"))
    )
    (net (code "47") (name "Net-(U$1-VBAT-Pad#22)") (class "Default")
      (node (ref "U$1") (pin "#22") (pinfunction "VBAT_#22") (pintype "power_in"))
      (node (ref "U$1") (pin "22") (pinfunction "VBAT_22") (pintype "power_in"))
      (node (ref "U$1") (pin "@22") (pinfunction "VBAT_@22") (pintype "power_in"))
    )
    (net (code "48") (name "Net-(U$1-WKP-Pad#5)") (class "Default")
      (node (ref "U$1") (pin "#5") (pinfunction "WKP_#5") (pintype "bidirectional"))
      (node (ref "U$1") (pin "5") (pinfunction "WKP_5") (pintype "bidirectional"))
      (node (ref "U$1") (pin "@5") (pinfunction "WKP_@5") (pintype "bidirectional"))
    )
    (net (code "49") (name "Net-(U$1-~{RST}-Pad#23)") (class "Default")
      (node (ref "U$1") (pin "#23") (pinfunction "~{RST}_#23") (pintype "bidirectional"))
      (node (ref "U$1") (pin "23") (pinfunction "~{RST}_23") (pintype "bidirectional"))
      (node (ref "U$1") (pin "@23") (pinfunction "~{RST}_@23") (pintype "bidirectional"))
    )
    (net (code "50") (name "unconnected-(F1-Pad1B)") (class "Default")
      (node (ref "F1") (pin "1B") (pinfunction "1B_1B") (pintype "passive"))
    )
    (net (code "51") (name "unconnected-(F1-Pad2B)") (class "Default")
      (node (ref "F1") (pin "2B") (pinfunction "2B_2B") (pintype "passive"))
    )
    (net (code "52") (name "unconnected-(JP3-Pad1)") (class "Default")
      (node (ref "JP3") (pin "1") (pinfunction "1_1") (pintype "passive"))
    )
    (net (code "53") (name "unconnected-(JP3-Pad2)") (class "Default")
      (node (ref "JP3") (pin "2") (pinfunction "2_2") (pintype "passive"))
    )
    (net (code "54") (name "unconnected-(JP3-Pad3)") (class "Default")
      (node (ref "JP3") (pin "3") (pinfunction "3_3") (pintype "passive"))
    )
    (net (code "55") (name "unconnected-(JP3-Pad4)") (class "Default")
      (node (ref "JP3") (pin "4") (pinfunction "4_4") (pintype "passive"))
    )
    (net (code "56") (name "unconnected-(JP3-Pad5)") (class "Default")
      (node (ref "JP3") (pin "5") (pinfunction "5_5") (pintype "passive"))
    )
    (net (code "57") (name "unconnected-(JP3-Pad6)") (class "Default")
      (node (ref "JP3") (pin "6") (pinfunction "6_6") (pintype "passive"))
    )
    (net (code "58") (name "unconnected-(JP3-Pad7)") (class "Default")
      (node (ref "JP3") (pin "7") (pinfunction "7_7") (pintype "passive"))
    )
    (net (code "59") (name "unconnected-(JP3-Pad8)") (class "Default")
      (node (ref "JP3") (pin "8") (pinfunction "8_8") (pintype "passive"))
    )
    (net (code "60") (name "unconnected-(JP3-Pad9)") (class "Default")
      (node (ref "JP3") (pin "9") (pinfunction "9_9") (pintype "passive"))
    )
    (net (code "61") (name "unconnected-(JP3-Pad10)") (class "Default")
      (node (ref "JP3") (pin "10") (pinfunction "10_10") (pintype "passive"))
    )
    (net (code "62") (name "unconnected-(JP4-Pad1)") (class "Default")
      (node (ref "JP4") (pin "1") (pinfunction "1_1") (pintype "passive"))
    )
    (net (code "63") (name "unconnected-(JP4-Pad2)") (class "Default")
      (node (ref "JP4") (pin "2") (pinfunction "2_2") (pintype "passive"))
    )
    (net (code "64") (name "unconnected-(JP4-Pad3)") (class "Default")
      (node (ref "JP4") (pin "3") (pinfunction "3_3") (pintype "passive"))
    )
    (net (code "65") (name "unconnected-(JP4-Pad4)") (class "Default")
      (node (ref "JP4") (pin "4") (pinfunction "4_4") (pintype "passive"))
    )
    (net (code "66") (name "unconnected-(JP4-Pad5)") (class "Default")
      (node (ref "JP4") (pin "5") (pinfunction "5_5") (pintype "passive"))
    )
    (net (code "67") (name "unconnected-(JP4-Pad6)") (class "Default")
      (node (ref "JP4") (pin "6") (pinfunction "6_6") (pintype "passive"))
    )
    (net (code "68") (name "unconnected-(JP4-Pad7)") (class "Default")
      (node (ref "JP4") (pin "7") (pinfunction "7_7") (pintype "passive"))
    )
    (net (code "69") (name "unconnected-(JP4-Pad8)") (class "Default")
      (node (ref "JP4") (pin "8") (pinfunction "8_8") (pintype "passive"))
    )
    (net (code "70") (name "unconnected-(JP4-Pad9)") (class "Default")
      (node (ref "JP4") (pin "9") (pinfunction "9_9") (pintype "passive"))
    )
    (net (code "71") (name "unconnected-(JP4-Pad10)") (class "Default")
      (node (ref "JP4") (pin "10") (pinfunction "10_10") (pintype "passive"))
    )
    (net (code "72") (name "unconnected-(JP5-Pad1)") (class "Default")
      (node (ref "JP5") (pin "1") (pinfunction "1_1") (pintype "passive"))
    )
    (net (code "73") (name "unconnected-(JP5-Pad2)") (class "Default")
      (node (ref "JP5") (pin "2") (pinfunction "2_2") (pintype "passive"))
    )
    (net (code "74") (name "unconnected-(JP5-Pad3)") (class "Default")
      (node (ref "JP5") (pin "3") (pinfunction "3_3") (pintype "passive"))
    )
    (net (code "75") (name "unconnected-(JP5-Pad4)") (class "Default")
      (node (ref "JP5") (pin "4") (pinfunction "4_4") (pintype "passive"))
    )
    (net (code "76") (name "unconnected-(JP5-Pad5)") (class "Default")
      (node (ref "JP5") (pin "5") (pinfunction "5_5") (pintype "passive"))
    )
    (net (code "77") (name "unconnected-(JP5-Pad6)") (class "Default")
      (node (ref "JP5") (pin "6") (pinfunction "6_6") (pintype "passive"))
    )
    (net (code "78") (name "unconnected-(JP5-Pad7)") (class "Default")
      (node (ref "JP5") (pin "7") (pinfunction "7_7") (pintype "passive"))
    )
    (net (code "79") (name "unconnected-(JP5-Pad8)") (class "Default")
      (node (ref "JP5") (pin "8") (pinfunction "8_8") (pintype "passive"))
    )
    (net (code "80") (name "unconnected-(JP5-Pad9)") (class "Default")
      (node (ref "JP5") (pin "9") (pinfunction "9_9") (pintype "passive"))
    )
    (net (code "81") (name "unconnected-(JP5-Pad10)") (class "Default")
      (node (ref "JP5") (pin "10") (pinfunction "10_10") (pintype "passive"))
    )
    (net (code "82") (name "unconnected-(JP6-Pad1)") (class "Default")
      (node (ref "JP6") (pin "1") (pinfunction "1_1") (pintype "passive"))
    )
    (net (code "83") (name "unconnected-(JP6-Pad2)") (class "Default")
      (node (ref "JP6") (pin "2") (pinfunction "2_2") (pintype "passive"))
    )
    (net (code "84") (name "unconnected-(JP6-Pad3)") (class "Default")
      (node (ref "JP6") (pin "3") (pinfunction "3_3") (pintype "passive"))
    )
    (net (code "85") (name "unconnected-(JP6-Pad4)") (class "Default")
      (node (ref "JP6") (pin "4") (pinfunction "4_4") (pintype "passive"))
    )
    (net (code "86") (name "unconnected-(JP6-Pad5)") (class "Default")
      (node (ref "JP6") (pin "5") (pinfunction "5_5") (pintype "passive"))
    )
    (net (code "87") (name "unconnected-(JP6-Pad6)") (class "Default")
      (node (ref "JP6") (pin "6") (pinfunction "6_6") (pintype "passive"))
    )
    (net (code "88") (name "unconnected-(JP6-Pad7)") (class "Default")
      (node (ref "JP6") (pin "7") (pinfunction "7_7") (pintype "passive"))
    )
    (net (code "89") (name "unconnected-(JP6-Pad8)") (class "Default")
      (node (ref "JP6") (pin "8") (pinfunction "8_8") (pintype "passive"))
    )
    (net (code "90") (name "unconnected-(JP6-Pad9)") (class "Default")
      (node (ref "JP6") (pin "9") (pinfunction "9_9") (pintype "passive"))
    )
    (net (code "91") (name "unconnected-(JP6-Pad10)") (class "Default")
      (node (ref "JP6") (pin "10") (pinfunction "10_10") (pintype "passive"))
    )
    (net (code "92") (name "unconnected-(JP7-Pad1)") (class "Default")
      (node (ref "JP7") (pin "1") (pinfunction "1_1") (pintype "passive"))
    )
    (net (code "93") (name "unconnected-(JP7-Pad2)") (class "Default")
      (node (ref "JP7") (pin "2") (pinfunction "2_2") (pintype "passive"))
    )
    (net (code "94") (name "unconnected-(JP7-Pad3)") (class "Default")
      (node (ref "JP7") (pin "3") (pinfunction "3_3") (pintype "passive"))
    )
    (net (code "95") (name "unconnected-(JP7-Pad4)") (class "Default")
      (node (ref "JP7") (pin "4") (pinfunction "4_4") (pintype "passive"))
    )
    (net (code "96") (name "unconnected-(JP7-Pad5)") (class "Default")
      (node (ref "JP7") (pin "5") (pinfunction "5_5") (pintype "passive"))
    )
    (net (code "97") (name "unconnected-(JP7-Pad6)") (class "Default")
      (node (ref "JP7") (pin "6") (pinfunction "6_6") (pintype "passive"))
    )
    (net (code "98") (name "unconnected-(JP7-Pad7)") (class "Default")
      (node (ref "JP7") (pin "7") (pinfunction "7_7") (pintype "passive"))
    )
    (net (code "99") (name "unconnected-(JP7-Pad8)") (class "Default")
      (node (ref "JP7") (pin "8") (pinfunction "8_8") (pintype "passive"))
    )
    (net (code "100") (name "unconnected-(JP7-Pad9)") (class "Default")
      (node (ref "JP7") (pin "9") (pinfunction "9_9") (pintype "passive"))
    )
    (net (code "101") (name "unconnected-(JP7-Pad10)") (class "Default")
      (node (ref "JP7") (pin "10") (pinfunction "10_10") (pintype "passive"))
    )
    (net (code "102") (name "unconnected-(JP8-Pad1)") (class "Default")
      (node (ref "JP8") (pin "1") (pinfunction "1_1") (pintype "passive"))
    )
    (net (code "103") (name "unconnected-(JP8-Pad2)") (class "Default")
      (node (ref "JP8") (pin "2") (pinfunction "2_2") (pintype "passive"))
    )
    (net (code "104") (name "unconnected-(JP8-Pad3)") (class "Default")
      (node (ref "JP8") (pin "3") (pinfunction "3_3") (pintype "passive"))
    )
    (net (code "105") (name "unconnected-(JP8-Pad4)") (class "Default")
      (node (ref "JP8") (pin "4") (pinfunction "4_4") (pintype "passive"))
    )
    (net (code "106") (name "unconnected-(JP8-Pad5)") (class "Default")
      (node (ref "JP8") (pin "5") (pinfunction "5_5") (pintype "passive"))
    )
    (net (code "107") (name "unconnected-(JP8-Pad6)") (class "Default")
      (node (ref "JP8") (pin "6") (pinfunction "6_6") (pintype "passive"))
    )
    (net (code "108") (name "unconnected-(JP8-Pad7)") (class "Default")
      (node (ref "JP8") (pin "7") (pinfunction "7_7") (pintype "passive"))
    )
    (net (code "109") (name "unconnected-(JP8-Pad8)") (class "Default")
      (node (ref "JP8") (pin "8") (pinfunction "8_8") (pintype "passive"))
    )
    (net (code "110") (name "unconnected-(JP8-Pad9)") (class "Default")
      (node (ref "JP8") (pin "9") (pinfunction "9_9") (pintype "passive"))
    )
    (net (code "111") (name "unconnected-(JP8-Pad10)") (class "Default")
      (node (ref "JP8") (pin "10") (pinfunction "10_10") (pintype "passive"))
    )
    (net (code "112") (name "unconnected-(JP9-Pad1)") (class "Default")
      (node (ref "JP9") (pin "1") (pinfunction "1_1") (pintype "passive"))
    )
    (net (code "113") (name "unconnected-(JP9-Pad2)") (class "Default")
      (node (ref "JP9") (pin "2") (pinfunction "2_2") (pintype "passive"))
    )
    (net (code "114") (name "unconnected-(JP9-Pad3)") (class "Default")
      (node (ref "JP9") (pin "3") (pinfunction "3_3") (pintype "passive"))
    )
    (net (code "115") (name "unconnected-(JP9-Pad4)") (class "Default")
      (node (ref "JP9") (pin "4") (pinfunction "4_4") (pintype "passive"))
    )
    (net (code "116") (name "unconnected-(JP9-Pad5)") (class "Default")
      (node (ref "JP9") (pin "5") (pinfunction "5_5") (pintype "passive"))
    )
    (net (code "117") (name "unconnected-(JP9-Pad6)") (class "Default")
      (node (ref "JP9") (pin "6") (pinfunction "6_6") (pintype "passive"))
    )
    (net (code "118") (name "unconnected-(JP9-Pad7)") (class "Default")
      (node (ref "JP9") (pin "7") (pinfunction "7_7") (pintype "passive"))
    )
    (net (code "119") (name "unconnected-(JP9-Pad8)") (class "Default")
      (node (ref "JP9") (pin "8") (pinfunction "8_8") (pintype "passive"))
    )
    (net (code "120") (name "unconnected-(JP9-Pad9)") (class "Default")
      (node (ref "JP9") (pin "9") (pinfunction "9_9") (pintype "passive"))
    )
    (net (code "121") (name "unconnected-(JP9-Pad10)") (class "Default")
      (node (ref "JP9") (pin "10") (pinfunction "10_10") (pintype "passive"))
    )
    (net (code "122") (name "unconnected-(JP10-Pad1)") (class "Default")
      (node (ref "JP10") (pin "1") (pinfunction "1_1") (pintype "passive"))
    )
    (net (code "123") (name "unconnected-(JP10-Pad2)") (class "Default")
      (node (ref "JP10") (pin "2") (pinfunction "2_2") (pintype "passive"))
    )
    (net (code "124") (name "unconnected-(JP10-Pad3)") (class "Default")
      (node (ref "JP10") (pin "3") (pinfunction "3_3") (pintype "passive"))
    )
    (net (code "125") (name "unconnected-(JP10-Pad4)") (class "Default")
      (node (ref "JP10") (pin "4") (pinfunction "4_4") (pintype "passive"))
    )
    (net (code "126") (name "unconnected-(JP10-Pad5)") (class "Default")
      (node (ref "JP10") (pin "5") (pinfunction "5_5") (pintype "passive"))
    )
    (net (code "127") (name "unconnected-(JP10-Pad6)") (class "Default")
      (node (ref "JP10") (pin "6") (pinfunction "6_6") (pintype "passive"))
    )
    (net (code "128") (name "unconnected-(JP10-Pad7)") (class "Default")
      (node (ref "JP10") (pin "7") (pinfunction "7_7") (pintype "passive"))
    )
    (net (code "129") (name "unconnected-(JP10-Pad8)") (class "Default")
      (node (ref "JP10") (pin "8") (pinfunction "8_8") (pintype "passive"))
    )
    (net (code "130") (name "unconnected-(JP10-Pad9)") (class "Default")
      (node (ref "JP10") (pin "9") (pinfunction "9_9") (pintype "passive"))
    )
    (net (code "131") (name "unconnected-(JP10-Pad10)") (class "Default")
      (node (ref "JP10") (pin "10") (pinfunction "10_10") (pintype "passive"))
    )
    (net (code "132") (name "unconnected-(JP11-Pad1)") (class "Default")
      (node (ref "JP11") (pin "1") (pinfunction "1_1") (pintype "passive"))
    )
    (net (code "133") (name "unconnected-(JP11-Pad2)") (class "Default")
      (node (ref "JP11") (pin "2") (pinfunction "2_2") (pintype "passive"))
    )
    (net (code "134") (name "unconnected-(JP11-Pad3)") (class "Default")
      (node (ref "JP11") (pin "3") (pinfunction "3_3") (pintype "passive"))
    )
    (net (code "135") (name "unconnected-(JP11-Pad4)") (class "Default")
      (node (ref "JP11") (pin "4") (pinfunction "4_4") (pintype "passive"))
    )
    (net (code "136") (name "unconnected-(JP11-Pad5)") (class "Default")
      (node (ref "JP11") (pin "5") (pinfunction "5_5") (pintype "passive"))
    )
    (net (code "137") (name "unconnected-(JP11-Pad6)") (class "Default")
      (node (ref "JP11") (pin "6") (pinfunction "6_6") (pintype "passive"))
    )
    (net (code "138") (name "unconnected-(JP11-Pad7)") (class "Default")
      (node (ref "JP11") (pin "7") (pinfunction "7_7") (pintype "passive"))
    )
    (net (code "139") (name "unconnected-(JP11-Pad8)") (class "Default")
      (node (ref "JP11") (pin "8") (pinfunction "8_8") (pintype "passive"))
    )
    (net (code "140") (name "unconnected-(JP11-Pad9)") (class "Default")
      (node (ref "JP11") (pin "9") (pinfunction "9_9") (pintype "passive"))
    )
    (net (code "141") (name "unconnected-(JP11-Pad10)") (class "Default")
      (node (ref "JP11") (pin "10") (pinfunction "10_10") (pintype "passive"))
    )
    (net (code "142") (name "unconnected-(JP12-Pad1)") (class "Default")
      (node (ref "JP12") (pin "1") (pinfunction "1_1") (pintype "passive"))
    )
    (net (code "143") (name "unconnected-(JP12-Pad2)") (class "Default")
      (node (ref "JP12") (pin "2") (pinfunction "2_2") (pintype "passive"))
    )
    (net (code "144") (name "unconnected-(JP12-Pad3)") (class "Default")
      (node (ref "JP12") (pin "3") (pinfunction "3_3") (pintype "passive"))
    )
    (net (code "145") (name "unconnected-(JP12-Pad4)") (class "Default")
      (node (ref "JP12") (pin "4") (pinfunction "4_4") (pintype "passive"))
    )
    (net (code "146") (name "unconnected-(JP12-Pad5)") (class "Default")
      (node (ref "JP12") (pin "5") (pinfunction "5_5") (pintype "passive"))
    )
    (net (code "147") (name "unconnected-(JP12-Pad6)") (class "Default")
      (node (ref "JP12") (pin "6") (pinfunction "6_6") (pintype "passive"))
    )
    (net (code "148") (name "unconnected-(JP12-Pad7)") (class "Default")
      (node (ref "JP12") (pin "7") (pinfunction "7_7") (pintype "passive"))
    )
    (net (code "149") (name "unconnected-(JP12-Pad8)") (class "Default")
      (node (ref "JP12") (pin "8") (pinfunction "8_8") (pintype "passive"))
    )
    (net (code "150") (name "unconnected-(JP12-Pad9)") (class "Default")
      (node (ref "JP12") (pin "9") (pinfunction "9_9") (pintype "passive"))
    )
    (net (code "151") (name "unconnected-(JP12-Pad10)") (class "Default")
      (node (ref "JP12") (pin "10") (pinfunction "10_10") (pintype "passive"))
    )
    (net (code "152") (name "unconnected-(JP13-Pad1)") (class "Default")
      (node (ref "JP13") (pin "1") (pinfunction "1_1") (pintype "passive"))
    )
    (net (code "153") (name "unconnected-(JP13-Pad2)") (class "Default")
      (node (ref "JP13") (pin "2") (pinfunction "2_2") (pintype "passive"))
    )
    (net (code "154") (name "unconnected-(JP13-Pad3)") (class "Default")
      (node (ref "JP13") (pin "3") (pinfunction "3_3") (pintype "passive"))
    )
    (net (code "155") (name "unconnected-(JP13-Pad4)") (class "Default")
      (node (ref "JP13") (pin "4") (pinfunction "4_4") (pintype "passive"))
    )
    (net (code "156") (name "unconnected-(JP13-Pad5)") (class "Default")
      (node (ref "JP13") (pin "5") (pinfunction "5_5") (pintype "passive"))
    )
    (net (code "157") (name "unconnected-(JP13-Pad6)") (class "Default")
      (node (ref "JP13") (pin "6") (pinfunction "6_6") (pintype "passive"))
    )
    (net (code "158") (name "unconnected-(JP13-Pad7)") (class "Default")
      (node (ref "JP13") (pin "7") (pinfunction "7_7") (pintype "passive"))
    )
    (net (code "159") (name "unconnected-(JP13-Pad8)") (class "Default")
      (node (ref "JP13") (pin "8") (pinfunction "8_8") (pintype "passive"))
    )
    (net (code "160") (name "unconnected-(JP13-Pad9)") (class "Default")
      (node (ref "JP13") (pin "9") (pinfunction "9_9") (pintype "passive"))
    )
    (net (code "161") (name "unconnected-(JP13-Pad10)") (class "Default")
      (node (ref "JP13") (pin "10") (pinfunction "10_10") (pintype "passive"))
    )
    (net (code "162") (name "unconnected-(JP14-Pad1)") (class "Default")
      (node (ref "JP14") (pin "1") (pinfunction "1_1") (pintype "passive"))
    )
    (net (code "163") (name "unconnected-(JP14-Pad2)") (class "Default")
      (node (ref "JP14") (pin "2") (pinfunction "2_2") (pintype "passive"))
    )
    (net (code "164") (name "unconnected-(JP14-Pad3)") (class "Default")
      (node (ref "JP14") (pin "3") (pinfunction "3_3") (pintype "passive"))
    )
    (net (code "165") (name "unconnected-(JP14-Pad4)") (class "Default")
      (node (ref "JP14") (pin "4") (pinfunction "4_4") (pintype "passive"))
    )
    (net (code "166") (name "unconnected-(JP14-Pad5)") (class "Default")
      (node (ref "JP14") (pin "5") (pinfunction "5_5") (pintype "passive"))
    )
    (net (code "167") (name "unconnected-(JP14-Pad6)") (class "Default")
      (node (ref "JP14") (pin "6") (pinfunction "6_6") (pintype "passive"))
    )
    (net (code "168") (name "unconnected-(JP14-Pad7)") (class "Default")
      (node (ref "JP14") (pin "7") (pinfunction "7_7") (pintype "passive"))
    )
    (net (code "169") (name "unconnected-(JP14-Pad8)") (class "Default")
      (node (ref "JP14") (pin "8") (pinfunction "8_8") (pintype "passive"))
    )
    (net (code "170") (name "unconnected-(JP14-Pad9)") (class "Default")
      (node (ref "JP14") (pin "9") (pinfunction "9_9") (pintype "passive"))
    )
    (net (code "171") (name "unconnected-(JP14-Pad10)") (class "Default")
      (node (ref "JP14") (pin "10") (pinfunction "10_10") (pintype "passive"))
    )
    (net (code "172") (name "unconnected-(JP15-Pad1)") (class "Default")
      (node (ref "JP15") (pin "1") (pinfunction "1_1") (pintype "passive"))
    )
    (net (code "173") (name "unconnected-(JP15-Pad2)") (class "Default")
      (node (ref "JP15") (pin "2") (pinfunction "2_2") (pintype "passive"))
    )
    (net (code "174") (name "unconnected-(JP15-Pad3)") (class "Default")
      (node (ref "JP15") (pin "3") (pinfunction "3_3") (pintype "passive"))
    )
    (net (code "175") (name "unconnected-(JP15-Pad4)") (class "Default")
      (node (ref "JP15") (pin "4") (pinfunction "4_4") (pintype "passive"))
    )
    (net (code "176") (name "unconnected-(JP15-Pad5)") (class "Default")
      (node (ref "JP15") (pin "5") (pinfunction "5_5") (pintype "passive"))
    )
    (net (code "177") (name "unconnected-(JP15-Pad6)") (class "Default")
      (node (ref "JP15") (pin "6") (pinfunction "6_6") (pintype "passive"))
    )
    (net (code "178") (name "unconnected-(JP15-Pad7)") (class "Default")
      (node (ref "JP15") (pin "7") (pinfunction "7_7") (pintype "passive"))
    )
    (net (code "179") (name "unconnected-(JP15-Pad8)") (class "Default")
      (node (ref "JP15") (pin "8") (pinfunction "8_8") (pintype "passive"))
    )
    (net (code "180") (name "unconnected-(JP15-Pad9)") (class "Default")
      (node (ref "JP15") (pin "9") (pinfunction "9_9") (pintype "passive"))
    )
    (net (code "181") (name "unconnected-(JP15-Pad10)") (class "Default")
      (node (ref "JP15") (pin "10") (pinfunction "10_10") (pintype "passive"))
    )
    (net (code "182") (name "unconnected-(JP16-Pad1)") (class "Default")
      (node (ref "JP16") (pin "1") (pinfunction "1_1") (pintype "passive"))
    )
    (net (code "183") (name "unconnected-(JP16-Pad2)") (class "Default")
      (node (ref "JP16") (pin "2") (pinfunction "2_2") (pintype "passive"))
    )
    (net (code "184") (name "unconnected-(JP16-Pad3)") (class "Default")
      (node (ref "JP16") (pin "3") (pinfunction "3_3") (pintype "passive"))
    )
    (net (code "185") (name "unconnected-(JP16-Pad4)") (class "Default")
      (node (ref "JP16") (pin "4") (pinfunction "4_4") (pintype "passive"))
    )
    (net (code "186") (name "unconnected-(JP16-Pad5)") (class "Default")
      (node (ref "JP16") (pin "5") (pinfunction "5_5") (pintype "passive"))
    )
    (net (code "187") (name "unconnected-(JP16-Pad6)") (class "Default")
      (node (ref "JP16") (pin "6") (pinfunction "6_6") (pintype "passive"))
    )
    (net (code "188") (name "unconnected-(JP16-Pad7)") (class "Default")
      (node (ref "JP16") (pin "7") (pinfunction "7_7") (pintype "passive"))
    )
    (net (code "189") (name "unconnected-(JP16-Pad8)") (class "Default")
      (node (ref "JP16") (pin "8") (pinfunction "8_8") (pintype "passive"))
    )
    (net (code "190") (name "unconnected-(JP16-Pad9)") (class "Default")
      (node (ref "JP16") (pin "9") (pinfunction "9_9") (pintype "passive"))
    )
    (net (code "191") (name "unconnected-(JP16-Pad10)") (class "Default")
      (node (ref "JP16") (pin "10") (pinfunction "10_10") (pintype "passive"))
    )
    (net (code "192") (name "unconnected-(JP17-Pad1)") (class "Default")
      (node (ref "JP17") (pin "1") (pinfunction "1_1") (pintype "passive"))
    )
    (net (code "193") (name "unconnected-(JP17-Pad2)") (class "Default")
      (node (ref "JP17") (pin "2") (pinfunction "2_2") (pintype "passive"))
    )
    (net (code "194") (name "unconnected-(JP17-Pad3)") (class "Default")
      (node (ref "JP17") (pin "3") (pinfunction "3_3") (pintype "passive"))
    )
    (net (code "195") (name "unconnected-(JP17-Pad4)") (class "Default")
      (node (ref "JP17") (pin "4") (pinfunction "4_4") (pintype "passive"))
    )
    (net (code "196") (name "unconnected-(JP17-Pad5)") (class "Default")
      (node (ref "JP17") (pin "5") (pinfunction "5_5") (pintype "passive"))
    )
    (net (code "197") (name "unconnected-(JP17-Pad6)") (class "Default")
      (node (ref "JP17") (pin "6") (pinfunction "6_6") (pintype "passive"))
    )
    (net (code "198") (name "unconnected-(JP17-Pad7)") (class "Default")
      (node (ref "JP17") (pin "7") (pinfunction "7_7") (pintype "passive"))
    )
    (net (code "199") (name "unconnected-(JP17-Pad8)") (class "Default")
      (node (ref "JP17") (pin "8") (pinfunction "8_8") (pintype "passive"))
    )
    (net (code "200") (name "unconnected-(JP17-Pad9)") (class "Default")
      (node (ref "JP17") (pin "9") (pinfunction "9_9") (pintype "passive"))
    )
    (net (code "201") (name "unconnected-(JP17-Pad10)") (class "Default")
      (node (ref "JP17") (pin "10") (pinfunction "10_10") (pintype "passive"))
    )
    (net (code "202") (name "unconnected-(JP18-Pad1)") (class "Default")
      (node (ref "JP18") (pin "1") (pinfunction "1_1") (pintype "passive"))
    )
    (net (code "203") (name "unconnected-(JP18-Pad2)") (class "Default")
      (node (ref "JP18") (pin "2") (pinfunction "2_2") (pintype "passive"))
    )
    (net (code "204") (name "unconnected-(JP18-Pad3)") (class "Default")
      (node (ref "JP18") (pin "3") (pinfunction "3_3") (pintype "passive"))
    )
    (net (code "205") (name "unconnected-(JP18-Pad4)") (class "Default")
      (node (ref "JP18") (pin "4") (pinfunction "4_4") (pintype "passive"))
    )
    (net (code "206") (name "unconnected-(JP18-Pad5)") (class "Default")
      (node (ref "JP18") (pin "5") (pinfunction "5_5") (pintype "passive"))
    )
    (net (code "207") (name "unconnected-(JP18-Pad6)") (class "Default")
      (node (ref "JP18") (pin "6") (pinfunction "6_6") (pintype "passive"))
    )
    (net (code "208") (name "unconnected-(JP18-Pad7)") (class "Default")
      (node (ref "JP18") (pin "7") (pinfunction "7_7") (pintype "passive"))
    )
    (net (code "209") (name "unconnected-(JP18-Pad8)") (class "Default")
      (node (ref "JP18") (pin "8") (pinfunction "8_8") (pintype "passive"))
    )
    (net (code "210") (name "unconnected-(JP18-Pad9)") (class "Default")
      (node (ref "JP18") (pin "9") (pinfunction "9_9") (pintype "passive"))
    )
    (net (code "211") (name "unconnected-(JP18-Pad10)") (class "Default")
      (node (ref "JP18") (pin "10") (pinfunction "10_10") (pintype "passive"))
    )
    (net (code "212") (name "unconnected-(JP19-Pad1)") (class "Default")
      (node (ref "JP19") (pin "1") (pinfunction "1_1") (pintype "passive"))
    )
    (net (code "213") (name "unconnected-(JP19-Pad2)") (class "Default")
      (node (ref "JP19") (pin "2") (pinfunction "2_2") (pintype "passive"))
    )
    (net (code "214") (name "unconnected-(JP19-Pad3)") (class "Default")
      (node (ref "JP19") (pin "3") (pinfunction "3_3") (pintype "passive"))
    )
    (net (code "215") (name "unconnected-(JP19-Pad4)") (class "Default")
      (node (ref "JP19") (pin "4") (pinfunction "4_4") (pintype "passive"))
    )
    (net (code "216") (name "unconnected-(JP19-Pad5)") (class "Default")
      (node (ref "JP19") (pin "5") (pinfunction "5_5") (pintype "passive"))
    )
    (net (code "217") (name "unconnected-(JP19-Pad6)") (class "Default")
      (node (ref "JP19") (pin "6") (pinfunction "6_6") (pintype "passive"))
    )
    (net (code "218") (name "unconnected-(JP19-Pad7)") (class "Default")
      (node (ref "JP19") (pin "7") (pinfunction "7_7") (pintype "passive"))
    )
    (net (code "219") (name "unconnected-(JP19-Pad8)") (class "Default")
      (node (ref "JP19") (pin "8") (pinfunction "8_8") (pintype "passive"))
    )
    (net (code "220") (name "unconnected-(JP19-Pad9)") (class "Default")
      (node (ref "JP19") (pin "9") (pinfunction "9_9") (pintype "passive"))
    )
    (net (code "221") (name "unconnected-(JP19-Pad10)") (class "Default")
      (node (ref "JP19") (pin "10") (pinfunction "10_10") (pintype "passive"))
    )
    (net (code "222") (name "unconnected-(JP20-Pad1)") (class "Default")
      (node (ref "JP20") (pin "1") (pinfunction "1_1") (pintype "passive"))
    )
    (net (code "223") (name "unconnected-(JP20-Pad2)") (class "Default")
      (node (ref "JP20") (pin "2") (pinfunction "2_2") (pintype "passive"))
    )
    (net (code "224") (name "unconnected-(JP20-Pad3)") (class "Default")
      (node (ref "JP20") (pin "3") (pinfunction "3_3") (pintype "passive"))
    )
    (net (code "225") (name "unconnected-(JP20-Pad4)") (class "Default")
      (node (ref "JP20") (pin "4") (pinfunction "4_4") (pintype "passive"))
    )
    (net (code "226") (name "unconnected-(JP20-Pad5)") (class "Default")
      (node (ref "JP20") (pin "5") (pinfunction "5_5") (pintype "passive"))
    )
    (net (code "227") (name "unconnected-(JP20-Pad6)") (class "Default")
      (node (ref "JP20") (pin "6") (pinfunction "6_6") (pintype "passive"))
    )
    (net (code "228") (name "unconnected-(JP20-Pad7)") (class "Default")
      (node (ref "JP20") (pin "7") (pinfunction "7_7") (pintype "passive"))
    )
    (net (code "229") (name "unconnected-(JP20-Pad8)") (class "Default")
      (node (ref "JP20") (pin "8") (pinfunction "8_8") (pintype "passive"))
    )
    (net (code "230") (name "unconnected-(JP20-Pad9)") (class "Default")
      (node (ref "JP20") (pin "9") (pinfunction "9_9") (pintype "passive"))
    )
    (net (code "231") (name "unconnected-(JP20-Pad10)") (class "Default")
      (node (ref "JP20") (pin "10") (pinfunction "10_10") (pintype "passive"))
    )
    (net (code "232") (name "unconnected-(JP21-Pad1)") (class "Default")
      (node (ref "JP21") (pin "1") (pinfunction "1_1") (pintype "passive"))
    )
    (net (code "233") (name "unconnected-(JP21-Pad2)") (class "Default")
      (node (ref "JP21") (pin "2") (pinfunction "2_2") (pintype "passive"))
    )
    (net (code "234") (name "unconnected-(JP21-Pad3)") (class "Default")
      (node (ref "JP21") (pin "3") (pinfunction "3_3") (pintype "passive"))
    )
    (net (code "235") (name "unconnected-(JP21-Pad4)") (class "Default")
      (node (ref "JP21") (pin "4") (pinfunction "4_4") (pintype "passive"))
    )
    (net (code "236") (name "unconnected-(JP21-Pad5)") (class "Default")
      (node (ref "JP21") (pin "5") (pinfunction "5_5") (pintype "passive"))
    )
    (net (code "237") (name "unconnected-(JP21-Pad6)") (class "Default")
      (node (ref "JP21") (pin "6") (pinfunction "6_6") (pintype "passive"))
    )
    (net (code "238") (name "unconnected-(JP21-Pad7)") (class "Default")
      (node (ref "JP21") (pin "7") (pinfunction "7_7") (pintype "passive"))
    )
    (net (code "239") (name "unconnected-(JP21-Pad8)") (class "Default")
      (node (ref "JP21") (pin "8") (pinfunction "8_8") (pintype "passive"))
    )
    (net (code "240") (name "unconnected-(JP21-Pad9)") (class "Default")
      (node (ref "JP21") (pin "9") (pinfunction "9_9") (pintype "passive"))
    )
    (net (code "241") (name "unconnected-(JP21-Pad10)") (class "Default")
      (node (ref "JP21") (pin "10") (pinfunction "10_10") (pintype "passive"))
    )
    (net (code "242") (name "unconnected-(JP22-Pad1)") (class "Default")
      (node (ref "JP22") (pin "1") (pinfunction "1_1") (pintype "passive"))
    )
    (net (code "243") (name "unconnected-(JP22-Pad2)") (class "Default")
      (node (ref "JP22") (pin "2") (pinfunction "2_2") (pintype "passive"))
    )
    (net (code "244") (name "unconnected-(JP22-Pad3)") (class "Default")
      (node (ref "JP22") (pin "3") (pinfunction "3_3") (pintype "passive"))
    )
    (net (code "245") (name "unconnected-(JP22-Pad4)") (class "Default")
      (node (ref "JP22") (pin "4") (pinfunction "4_4") (pintype "passive"))
    )
    (net (code "246") (name "unconnected-(JP22-Pad5)") (class "Default")
      (node (ref "JP22") (pin "5") (pinfunction "5_5") (pintype "passive"))
    )
    (net (code "247") (name "unconnected-(JP22-Pad6)") (class "Default")
      (node (ref "JP22") (pin "6") (pinfunction "6_6") (pintype "passive"))
    )
    (net (code "248") (name "unconnected-(JP22-Pad7)") (class "Default")
      (node (ref "JP22") (pin "7") (pinfunction "7_7") (pintype "passive"))
    )
    (net (code "249") (name "unconnected-(JP22-Pad8)") (class "Default")
      (node (ref "JP22") (pin "8") (pinfunction "8_8") (pintype "passive"))
    )
    (net (code "250") (name "unconnected-(JP22-Pad9)") (class "Default")
      (node (ref "JP22") (pin "9") (pinfunction "9_9") (pintype "passive"))
    )
    (net (code "251") (name "unconnected-(JP22-Pad10)") (class "Default")
      (node (ref "JP22") (pin "10") (pinfunction "10_10") (pintype "passive"))
    )
    (net (code "252") (name "unconnected-(JP23-Pad1)") (class "Default")
      (node (ref "JP23") (pin "1") (pinfunction "1_1") (pintype "passive"))
    )
    (net (code "253") (name "unconnected-(JP23-Pad2)") (class "Default")
      (node (ref "JP23") (pin "2") (pinfunction "2_2") (pintype "passive"))
    )
    (net (code "254") (name "unconnected-(JP23-Pad3)") (class "Default")
      (node (ref "JP23") (pin "3") (pinfunction "3_3") (pintype "passive"))
    )
    (net (code "255") (name "unconnected-(JP23-Pad4)") (class "Default")
      (node (ref "JP23") (pin "4") (pinfunction "4_4") (pintype "passive"))
    )
    (net (code "256") (name "unconnected-(JP23-Pad5)") (class "Default")
      (node (ref "JP23") (pin "5") (pinfunction "5_5") (pintype "passive"))
    )
    (net (code "257") (name "unconnected-(JP23-Pad6)") (class "Default")
      (node (ref "JP23") (pin "6") (pinfunction "6_6") (pintype "passive"))
    )
    (net (code "258") (name "unconnected-(JP23-Pad7)") (class "Default")
      (node (ref "JP23") (pin "7") (pinfunction "7_7") (pintype "passive"))
    )
    (net (code "259") (name "unconnected-(JP23-Pad8)") (class "Default")
      (node (ref "JP23") (pin "8") (pinfunction "8_8") (pintype "passive"))
    )
    (net (code "260") (name "unconnected-(JP23-Pad9)") (class "Default")
      (node (ref "JP23") (pin "9") (pinfunction "9_9") (pintype "passive"))
    )
    (net (code "261") (name "unconnected-(JP23-Pad10)") (class "Default")
      (node (ref "JP23") (pin "10") (pinfunction "10_10") (pintype "passive"))
    )
    (net (code "262") (name "unconnected-(JP24-Pad1)") (class "Default")
      (node (ref "JP24") (pin "1") (pinfunction "1_1") (pintype "passive"))
    )
    (net (code "263") (name "unconnected-(JP24-Pad2)") (class "Default")
      (node (ref "JP24") (pin "2") (pinfunction "2_2") (pintype "passive"))
    )
    (net (code "264") (name "unconnected-(JP24-Pad3)") (class "Default")
      (node (ref "JP24") (pin "3") (pinfunction "3_3") (pintype "passive"))
    )
    (net (code "265") (name "unconnected-(JP24-Pad4)") (class "Default")
      (node (ref "JP24") (pin "4") (pinfunction "4_4") (pintype "passive"))
    )
    (net (code "266") (name "unconnected-(JP24-Pad5)") (class "Default")
      (node (ref "JP24") (pin "5") (pinfunction "5_5") (pintype "passive"))
    )
    (net (code "267") (name "unconnected-(JP24-Pad6)") (class "Default")
      (node (ref "JP24") (pin "6") (pinfunction "6_6") (pintype "passive"))
    )
    (net (code "268") (name "unconnected-(JP24-Pad7)") (class "Default")
      (node (ref "JP24") (pin "7") (pinfunction "7_7") (pintype "passive"))
    )
    (net (code "269") (name "unconnected-(JP24-Pad8)") (class "Default")
      (node (ref "JP24") (pin "8") (pinfunction "8_8") (pintype "passive"))
    )
    (net (code "270") (name "unconnected-(JP24-Pad9)") (class "Default")
      (node (ref "JP24") (pin "9") (pinfunction "9_9") (pintype "passive"))
    )
    (net (code "271") (name "unconnected-(JP24-Pad10)") (class "Default")
      (node (ref "JP24") (pin "10") (pinfunction "10_10") (pintype "passive"))
    )
    (net (code "272") (name "unconnected-(JP25-Pad1)") (class "Default")
      (node (ref "JP25") (pin "1") (pinfunction "1_1") (pintype "passive"))
    )
    (net (code "273") (name "unconnected-(JP25-Pad2)") (class "Default")
      (node (ref "JP25") (pin "2") (pinfunction "2_2") (pintype "passive"))
    )
    (net (code "274") (name "unconnected-(JP25-Pad3)") (class "Default")
      (node (ref "JP25") (pin "3") (pinfunction "3_3") (pintype "passive"))
    )
    (net (code "275") (name "unconnected-(JP25-Pad4)") (class "Default")
      (node (ref "JP25") (pin "4") (pinfunction "4_4") (pintype "passive"))
    )
    (net (code "276") (name "unconnected-(JP25-Pad5)") (class "Default")
      (node (ref "JP25") (pin "5") (pinfunction "5_5") (pintype "passive"))
    )
    (net (code "277") (name "unconnected-(JP25-Pad6)") (class "Default")
      (node (ref "JP25") (pin "6") (pinfunction "6_6") (pintype "passive"))
    )
    (net (code "278") (name "unconnected-(JP25-Pad7)") (class "Default")
      (node (ref "JP25") (pin "7") (pinfunction "7_7") (pintype "passive"))
    )
    (net (code "279") (name "unconnected-(JP25-Pad8)") (class "Default")
      (node (ref "JP25") (pin "8") (pinfunction "8_8") (pintype "passive"))
    )
    (net (code "280") (name "unconnected-(JP25-Pad9)") (class "Default")
      (node (ref "JP25") (pin "9") (pinfunction "9_9") (pintype "passive"))
    )
    (net (code "281") (name "unconnected-(JP25-Pad10)") (class "Default")
      (node (ref "JP25") (pin "10") (pinfunction "10_10") (pintype "passive"))
    )
    (net (code "282") (name "unconnected-(JP26-Pad1)") (class "Default")
      (node (ref "JP26") (pin "1") (pinfunction "1_1") (pintype "passive"))
    )
    (net (code "283") (name "unconnected-(JP26-Pad2)") (class "Default")
      (node (ref "JP26") (pin "2") (pinfunction "2_2") (pintype "passive"))
    )
    (net (code "284") (name "unconnected-(JP26-Pad3)") (class "Default")
      (node (ref "JP26") (pin "3") (pinfunction "3_3") (pintype "passive"))
    )
    (net (code "285") (name "unconnected-(JP26-Pad4)") (class "Default")
      (node (ref "JP26") (pin "4") (pinfunction "4_4") (pintype "passive"))
    )
    (net (code "286") (name "unconnected-(JP26-Pad5)") (class "Default")
      (node (ref "JP26") (pin "5") (pinfunction "5_5") (pintype "passive"))
    )
    (net (code "287") (name "unconnected-(JP26-Pad6)") (class "Default")
      (node (ref "JP26") (pin "6") (pinfunction "6_6") (pintype "passive"))
    )
    (net (code "288") (name "unconnected-(JP29-Pad1)") (class "Default")
      (node (ref "JP29") (pin "1") (pinfunction "1_1") (pintype "passive"))
    )
    (net (code "289") (name "unconnected-(JP29-Pad2)") (class "Default")
      (node (ref "JP29") (pin "2") (pinfunction "2_2") (pintype "passive"))
    )
    (net (code "290") (name "unconnected-(JP29-Pad3)") (class "Default")
      (node (ref "JP29") (pin "3") (pinfunction "3_3") (pintype "passive"))
    )
    (net (code "291") (name "unconnected-(JP29-Pad4)") (class "Default")
      (node (ref "JP29") (pin "4") (pinfunction "4_4") (pintype "passive"))
    )
    (net (code "292") (name "unconnected-(JP29-Pad5)") (class "Default")
      (node (ref "JP29") (pin "5") (pinfunction "5_5") (pintype "passive"))
    )
    (net (code "293") (name "unconnected-(JP29-Pad6)") (class "Default")
      (node (ref "JP29") (pin "6") (pinfunction "6_6") (pintype "passive"))
    )
  )
)
